# MAGI_sBoostPowerV2.net
KiCad netlist of a schematic drawn in Altium Designer
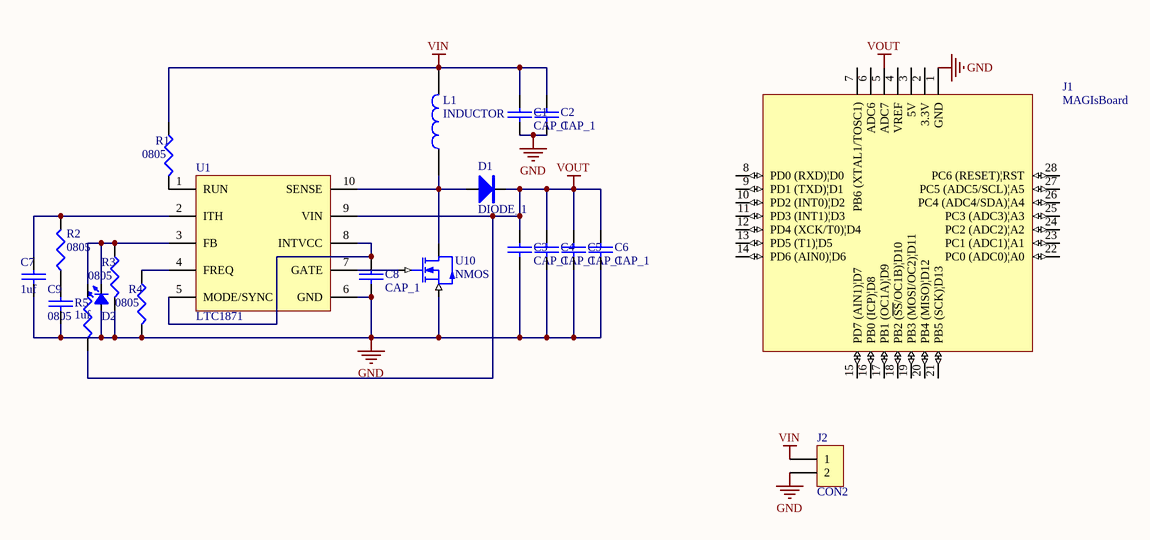
[diagram p0: MAGI'sBoostPowerV2.SchDoc]

(export (version "E")
  (design (tool "Eeschema 10.0.6"))
  (components
    (comp (ref "C1")
      (value "CAP_1")
      (footprint "C1206")
      (description "Capacitor")
      (libsource (lib "电容器") (part "CAP_1"))
    )
    (comp (ref "C2")
      (value "CAP_1")
      (footprint "C1206")
      (description "Capacitor")
      (libsource (lib "电容器") (part "CAP_1"))
    )
    (comp (ref "C3")
      (value "CAP_1")
      (footprint "C1210_N")
      (description "Capacitor")
      (libsource (lib "电容器") (part "CAP_1"))
    )
    (comp (ref "C4")
      (value "CAP_1")
      (footprint "C1210_N")
      (description "Capacitor")
      (libsource (lib "电容器") (part "CAP_1"))
    )
    (comp (ref "C5")
      (value "CAP_1")
      (footprint "C1206")
      (description "Capacitor")
      (libsource (lib "电容器") (part "CAP_1"))
    )
    (comp (ref "C6")
      (value "CAP_1")
      (footprint "C1206")
      (description "Capacitor")
      (libsource (lib "电容器") (part "CAP_1"))
    )
    (comp (ref "C7")
      (value "1uf")
      (footprint "6-0805_N")
      (description "Capacitor")
      (libsource (lib "电容器") (part "CAP_1"))
    )
    (comp (ref "C8")
      (value "CAP_1")
      (footprint "6-0805_n")
      (description "Capacitor")
      (libsource (lib "电容器") (part "CAP_1"))
    )
    (comp (ref "C9")
      (value "1uf")
      (footprint "6-0805_N")
      (description "Capacitor")
      (libsource (lib "电容器") (part "CAP_1"))
    )
    (comp (ref "D1")
      (value "DIODE_1")
      (footprint "SMB")
      (description "Diode")
      (libsource (lib "二极管") (part "DIODE_1"))
    )
    (comp (ref "D2")
      (value "LED_0805")
      (footprint "6-0805_n")
      (description "LED")
      (libsource (lib "SCH_Active") (part "LED_0805"))
    )
    (comp (ref "J1")
      (value "MAGIsBoard")
      (footprint "MAGIsBoard")
      (libsource (lib "MAGIsBoard") (part "MAGIsBoard"))
    )
    (comp (ref "J2")
      (value "CON2")
      (footprint "T-Mini")
      (description "Connector")
      (libsource (lib "CON系列") (part "CON2"))
    )
    (comp (ref "L1") (value "INDUCTOR") (footprint "10*10") (libsource (lib "汇总") (part "INDUCTOR")))
    (comp (ref "R1") (value "0805") (footprint "6-0805_N") (libsource (lib "电阻器") (part "RES1_1")))
    (comp (ref "R2") (value "0805") (footprint "6-0805_N") (libsource (lib "电阻器") (part "RES1_1")))
    (comp (ref "R3") (value "0805") (footprint "6-0805_N") (libsource (lib "电阻器") (part "RES1_1")))
    (comp (ref "R4") (value "0805") (footprint "6-0805_N") (libsource (lib "电阻器") (part "RES1_1")))
    (comp (ref "R5") (value "0805") (footprint "6-0805_N") (libsource (lib "电阻器") (part "RES1_1")))
    (comp (ref "U1") (value "LTC1871") (footprint "LTC1871") (libsource (lib "PMIC") (part "LTC1871")))
    (comp (ref "U10")
      (value "NMOS")
      (footprint "AOD4184")
      (description "TO252")
      (libsource (lib "MOSFET") (part "NMOS"))
    )
  )
  (nets
    (net (code "1") (name "GND") (class "Default")
      (node (ref "C1") (pin "2") (pinfunction "2_2") (pintype "passive"))
      (node (ref "C2") (pin "1") (pinfunction "1_1") (pintype "passive"))
      (node (ref "C3") (pin "1") (pinfunction "1_1") (pintype "passive"))
      (node (ref "C4") (pin "1") (pinfunction "1_1") (pintype "passive"))
      (node (ref "C5") (pin "1") (pinfunction "1_1") (pintype "passive"))
      (node (ref "C6") (pin "1") (pinfunction "1_1") (pintype "passive"))
      (node (ref "C7") (pin "1") (pinfunction "1_1") (pintype "passive"))
      (node (ref "C8") (pin "1") (pinfunction "1_1") (pintype "passive"))
      (node (ref "C9") (pin "1") (pinfunction "1_1") (pintype "passive"))
      (node (ref "D2") (pin "1") (pinfunction "A_1") (pintype "passive"))
      (node (ref "J1") (pin "1") (pinfunction "GND_1") (pintype "power_in"))
      (node (ref "J2") (pin "2") (pinfunction "2_2") (pintype "passive"))
      (node (ref "R3") (pin "2") (pinfunction "2_2") (pintype "passive"))
      (node (ref "R4") (pin "2") (pinfunction "2_2") (pintype "passive"))
      (node (ref "U1") (pin "6") (pinfunction "GND_6") (pintype "passive"))
      (node (ref "U10") (pin "3") (pinfunction "S_3") (pintype "input"))
    )
    (net (code "2") (name "Net-(C9-Pad2)") (class "Default")
      (node (ref "C9") (pin "2") (pinfunction "2_2") (pintype "passive"))
      (node (ref "R2") (pin "1") (pinfunction "1_1") (pintype "passive"))
    )
    (net (code "3") (name "Net-(D1-A)") (class "Default")
      (node (ref "D1") (pin "1") (pinfunction "A_1") (pintype "passive"))
      (node (ref "L1") (pin "1") (pinfunction "1_1") (pintype "passive"))
      (node (ref "U1") (pin "10") (pinfunction "SENSE_10") (pintype "passive"))
      (node (ref "U10") (pin "4") (pinfunction "D_4") (pintype "passive"))
    )
    (net (code "4") (name "Net-(D2-K)") (class "Default")
      (node (ref "D2") (pin "2") (pinfunction "K_2") (pintype "passive"))
      (node (ref "R3") (pin "1") (pinfunction "1_1") (pintype "passive"))
      (node (ref "R5") (pin "1") (pinfunction "1_1") (pintype "passive"))
      (node (ref "U1") (pin "3") (pinfunction "FB_3") (pintype "passive"))
    )
    (net (code "5") (name "Net-(U1-FREQ)") (class "Default")
      (node (ref "R4") (pin "1") (pinfunction "1_1") (pintype "passive"))
      (node (ref "U1") (pin "4") (pinfunction "FREQ_4") (pintype "passive"))
    )
    (net (code "6") (name "Net-(U1-GATE)") (class "Default")
      (node (ref "U1") (pin "7") (pinfunction "GATE_7") (pintype "passive"))
      (node (ref "U10") (pin "1") (pinfunction "G_1") (pintype "input"))
    )
    (net (code "7") (name "Net-(U1-INTVCC)") (class "Default")
      (node (ref "C8") (pin "2") (pinfunction "2_2") (pintype "passive"))
      (node (ref "U1") (pin "5") (pinfunction "MODE/SYNC_5") (pintype "passive"))
      (node (ref "U1") (pin "8") (pinfunction "INTVCC_8") (pintype "passive"))
    )
    (net (code "8") (name "Net-(U1-ITH)") (class "Default")
      (node (ref "C7") (pin "2") (pinfunction "2_2") (pintype "passive"))
      (node (ref "R2") (pin "2") (pinfunction "2_2") (pintype "passive"))
      (node (ref "U1") (pin "2") (pinfunction "ITH_2") (pintype "passive"))
    )
    (net (code "9") (name "Net-(U1-RUN)") (class "Default")
      (node (ref "R1") (pin "2") (pinfunction "2_2") (pintype "passive"))
      (node (ref "U1") (pin "1") (pinfunction "RUN_1") (pintype "passive"))
    )
    (net (code "10") (name "VIN") (class "Default")
      (node (ref "C1") (pin "1") (pinfunction "1_1") (pintype "passive"))
      (node (ref "C2") (pin "2") (pinfunction "2_2") (pintype "passive"))
      (node (ref "J2") (pin "1") (pinfunction "1_1") (pintype "passive"))
      (node (ref "L1") (pin "2") (pinfunction "2_2") (pintype "passive"))
      (node (ref "R1") (pin "1") (pinfunction "1_1") (pintype "passive"))
    )
    (net (code "11") (name "VOUT") (class "Default")
      (node (ref "C3") (pin "2") (pinfunction "2_2") (pintype "passive"))
      (node (ref "C4") (pin "2") (pinfunction "2_2") (pintype "passive"))
      (node (ref "C5") (pin "2") (pinfunction "2_2") (pintype "passive"))
      (node (ref "C6") (pin "2") (pinfunction "2_2") (pintype "passive"))
      (node (ref "D1") (pin "2") (pinfunction "K_2") (pintype "passive"))
      (node (ref "J1") (pin "5") (pinfunction "ADC7_5") (pintype "passive"))
      (node (ref "R5") (pin "2") (pinfunction "2_2") (pintype "passive"))
      (node (ref "U1") (pin "9") (pinfunction "VIN_9") (pintype "passive"))
    )
    (net (code "12") (name "unconnected-(J1-3.3V-Pad2)") (class "Default")
      (node (ref "J1") (pin "2") (pinfunction "3.3V_2") (pintype "power_in"))
    )
    (net (code "13") (name "unconnected-(J1-5V-Pad3)") (class "Default")
      (node (ref "J1") (pin "3") (pinfunction "5V_3") (pintype "power_in"))
    )
    (net (code "14") (name "unconnected-(J1-ADC6-Pad6)") (class "Default")
      (node (ref "J1") (pin "6") (pinfunction "ADC6_6") (pintype "passive"))
    )
    (net (code "15") (name "unconnected-(J1-PB0_(ICP)¦D8-Pad16)") (class "Default")
      (node (ref "J1") (pin "16") (pinfunction "PB0_(ICP)¦D8_16") (pintype "bidirectional"))
    )
    (net (code "16") (name "unconnected-(J1-PB1_(OC1A)¦D9-Pad17)") (class "Default")
      (node (ref "J1") (pin "17") (pinfunction "PB1_(OC1A)¦D9_17") (pintype "bidirectional"))
    )
    (net (code "17") (name "unconnected-(J1-PB2_(~{SS}{slash}OC1B)¦D10-Pad18)") (class "Default")
      (node (ref "J1") (pin "18") (pinfunction "PB2_(~{SS}/OC1B)¦D10_18") (pintype "bidirectional"))
    )
    (net (code "18") (name "unconnected-(J1-PB3_(MOSI{slash}OC2)¦D11-Pad19)") (class "Default")
      (node (ref "J1") (pin "19") (pinfunction "PB3_(MOSI/OC2)¦D11_19") (pintype "bidirectional"))
    )
    (net (code "19") (name "unconnected-(J1-PB4_(MISO)¦D12-Pad20)") (class "Default")
      (node (ref "J1") (pin "20") (pinfunction "PB4_(MISO)¦D12_20") (pintype "bidirectional"))
    )
    (net (code "20") (name "unconnected-(J1-PB5_(SCK)¦D13-Pad21)") (class "Default")
      (node (ref "J1") (pin "21") (pinfunction "PB5_(SCK)¦D13_21") (pintype "bidirectional"))
    )
    (net (code "21") (name "unconnected-(J1-PB6_(XTAL1{slash}TOSC1)-Pad7)") (class "Default")
      (node (ref "J1") (pin "7") (pinfunction "PB6_(XTAL1/TOSC1)_7") (pintype "passive"))
    )
    (net (code "22") (name "unconnected-(J1-PC0_(ADC0)¦A0-Pad22)") (class "Default")
      (node (ref "J1") (pin "22") (pinfunction "PC0_(ADC0)¦A0_22") (pintype "bidirectional"))
    )
    (net (code "23") (name "unconnected-(J1-PC1_(ADC1)¦A1-Pad23)") (class "Default")
      (node (ref "J1") (pin "23") (pinfunction "PC1_(ADC1)¦A1_23") (pintype "bidirectional"))
    )
    (net (code "24") (name "unconnected-(J1-PC2_(ADC2)¦A2-Pad24)") (class "Default")
      (node (ref "J1") (pin "24") (pinfunction "PC2_(ADC2)¦A2_24") (pintype "bidirectional"))
    )
    (net (code "25") (name "unconnected-(J1-PC3_(ADC3)¦A3-Pad25)") (class "Default")
      (node (ref "J1") (pin "25") (pinfunction "PC3_(ADC3)¦A3_25") (pintype "bidirectional"))
    )
    (net (code "26") (name "unconnected-(J1-PC4_(ADC4{slash}SDA)¦A4-Pad26)") (class "Default")
      (node (ref "J1") (pin "26") (pinfunction "PC4_(ADC4/SDA)¦A4_26") (pintype "bidirectional"))
    )
    (net (code "27") (name "unconnected-(J1-PC5_(ADC5{slash}SCL)¦A5-Pad27)") (class "Default")
      (node (ref "J1") (pin "27") (pinfunction "PC5_(ADC5/SCL)¦A5_27") (pintype "bidirectional"))
    )
    (net (code "28") (name "unconnected-(J1-PC6_(RESET)¦RST-Pad28)") (class "Default")
      (node (ref "J1") (pin "28") (pinfunction "PC6_(RESET)¦RST_28") (pintype "bidirectional"))
    )
    (net (code "29") (name "unconnected-(J1-PD0_(RXD)¦D0-Pad8)") (class "Default")
      (node (ref "J1") (pin "8") (pinfunction "PD0_(RXD)¦D0_8") (pintype "bidirectional"))
    )
    (net (code "30") (name "unconnected-(J1-PD1_(TXD)¦D1-Pad9)") (class "Default")
      (node (ref "J1") (pin "9") (pinfunction "PD1_(TXD)¦D1_9") (pintype "bidirectional"))
    )
    (net (code "31") (name "unconnected-(J1-PD2_(INT0)¦D2-Pad10)") (class "Default")
      (node (ref "J1") (pin "10") (pinfunction "PD2_(INT0)¦D2_10") (pintype "bidirectional"))
    )
    (net (code "32") (name "unconnected-(J1-PD3_(INT1)¦D3-Pad11)") (class "Default")
      (node (ref "J1") (pin "11") (pinfunction "PD3_(INT1)¦D3_11") (pintype "bidirectional"))
    )
    (net (code "33") (name "unconnected-(J1-PD4_(XCK{slash}T0)¦D4-Pad12)") (class "Default")
      (node (ref "J1") (pin "12") (pinfunction "PD4_(XCK/T0)¦D4_12") (pintype "bidirectional"))
    )
    (net (code "34") (name "unconnected-(J1-PD5_(T1)¦D5-Pad13)") (class "Default")
      (node (ref "J1") (pin "13") (pinfunction "PD5_(T1)¦D5_13") (pintype "bidirectional"))
    )
    (net (code "35") (name "unconnected-(J1-PD6_(AIN0)¦D6-Pad14)") (class "Default")
      (node (ref "J1") (pin "14") (pinfunction "PD6_(AIN0)¦D6_14") (pintype "bidirectional"))
    )
    (net (code "36") (name "unconnected-(J1-PD7_(AIN1)¦D7-Pad15)") (class "Default")
      (node (ref "J1") (pin "15") (pinfunction "PD7_(AIN1)¦D7_15") (pintype "bidirectional"))
    )
    (net (code "37") (name "unconnected-(J1-VREF-Pad4)") (class "Default")
      (node (ref "J1") (pin "4") (pinfunction "VREF_4") (pintype "passive"))
    )
  )
)
